# LED_Connection.net
KiCad netlist of a schematic drawn in Altium Designer
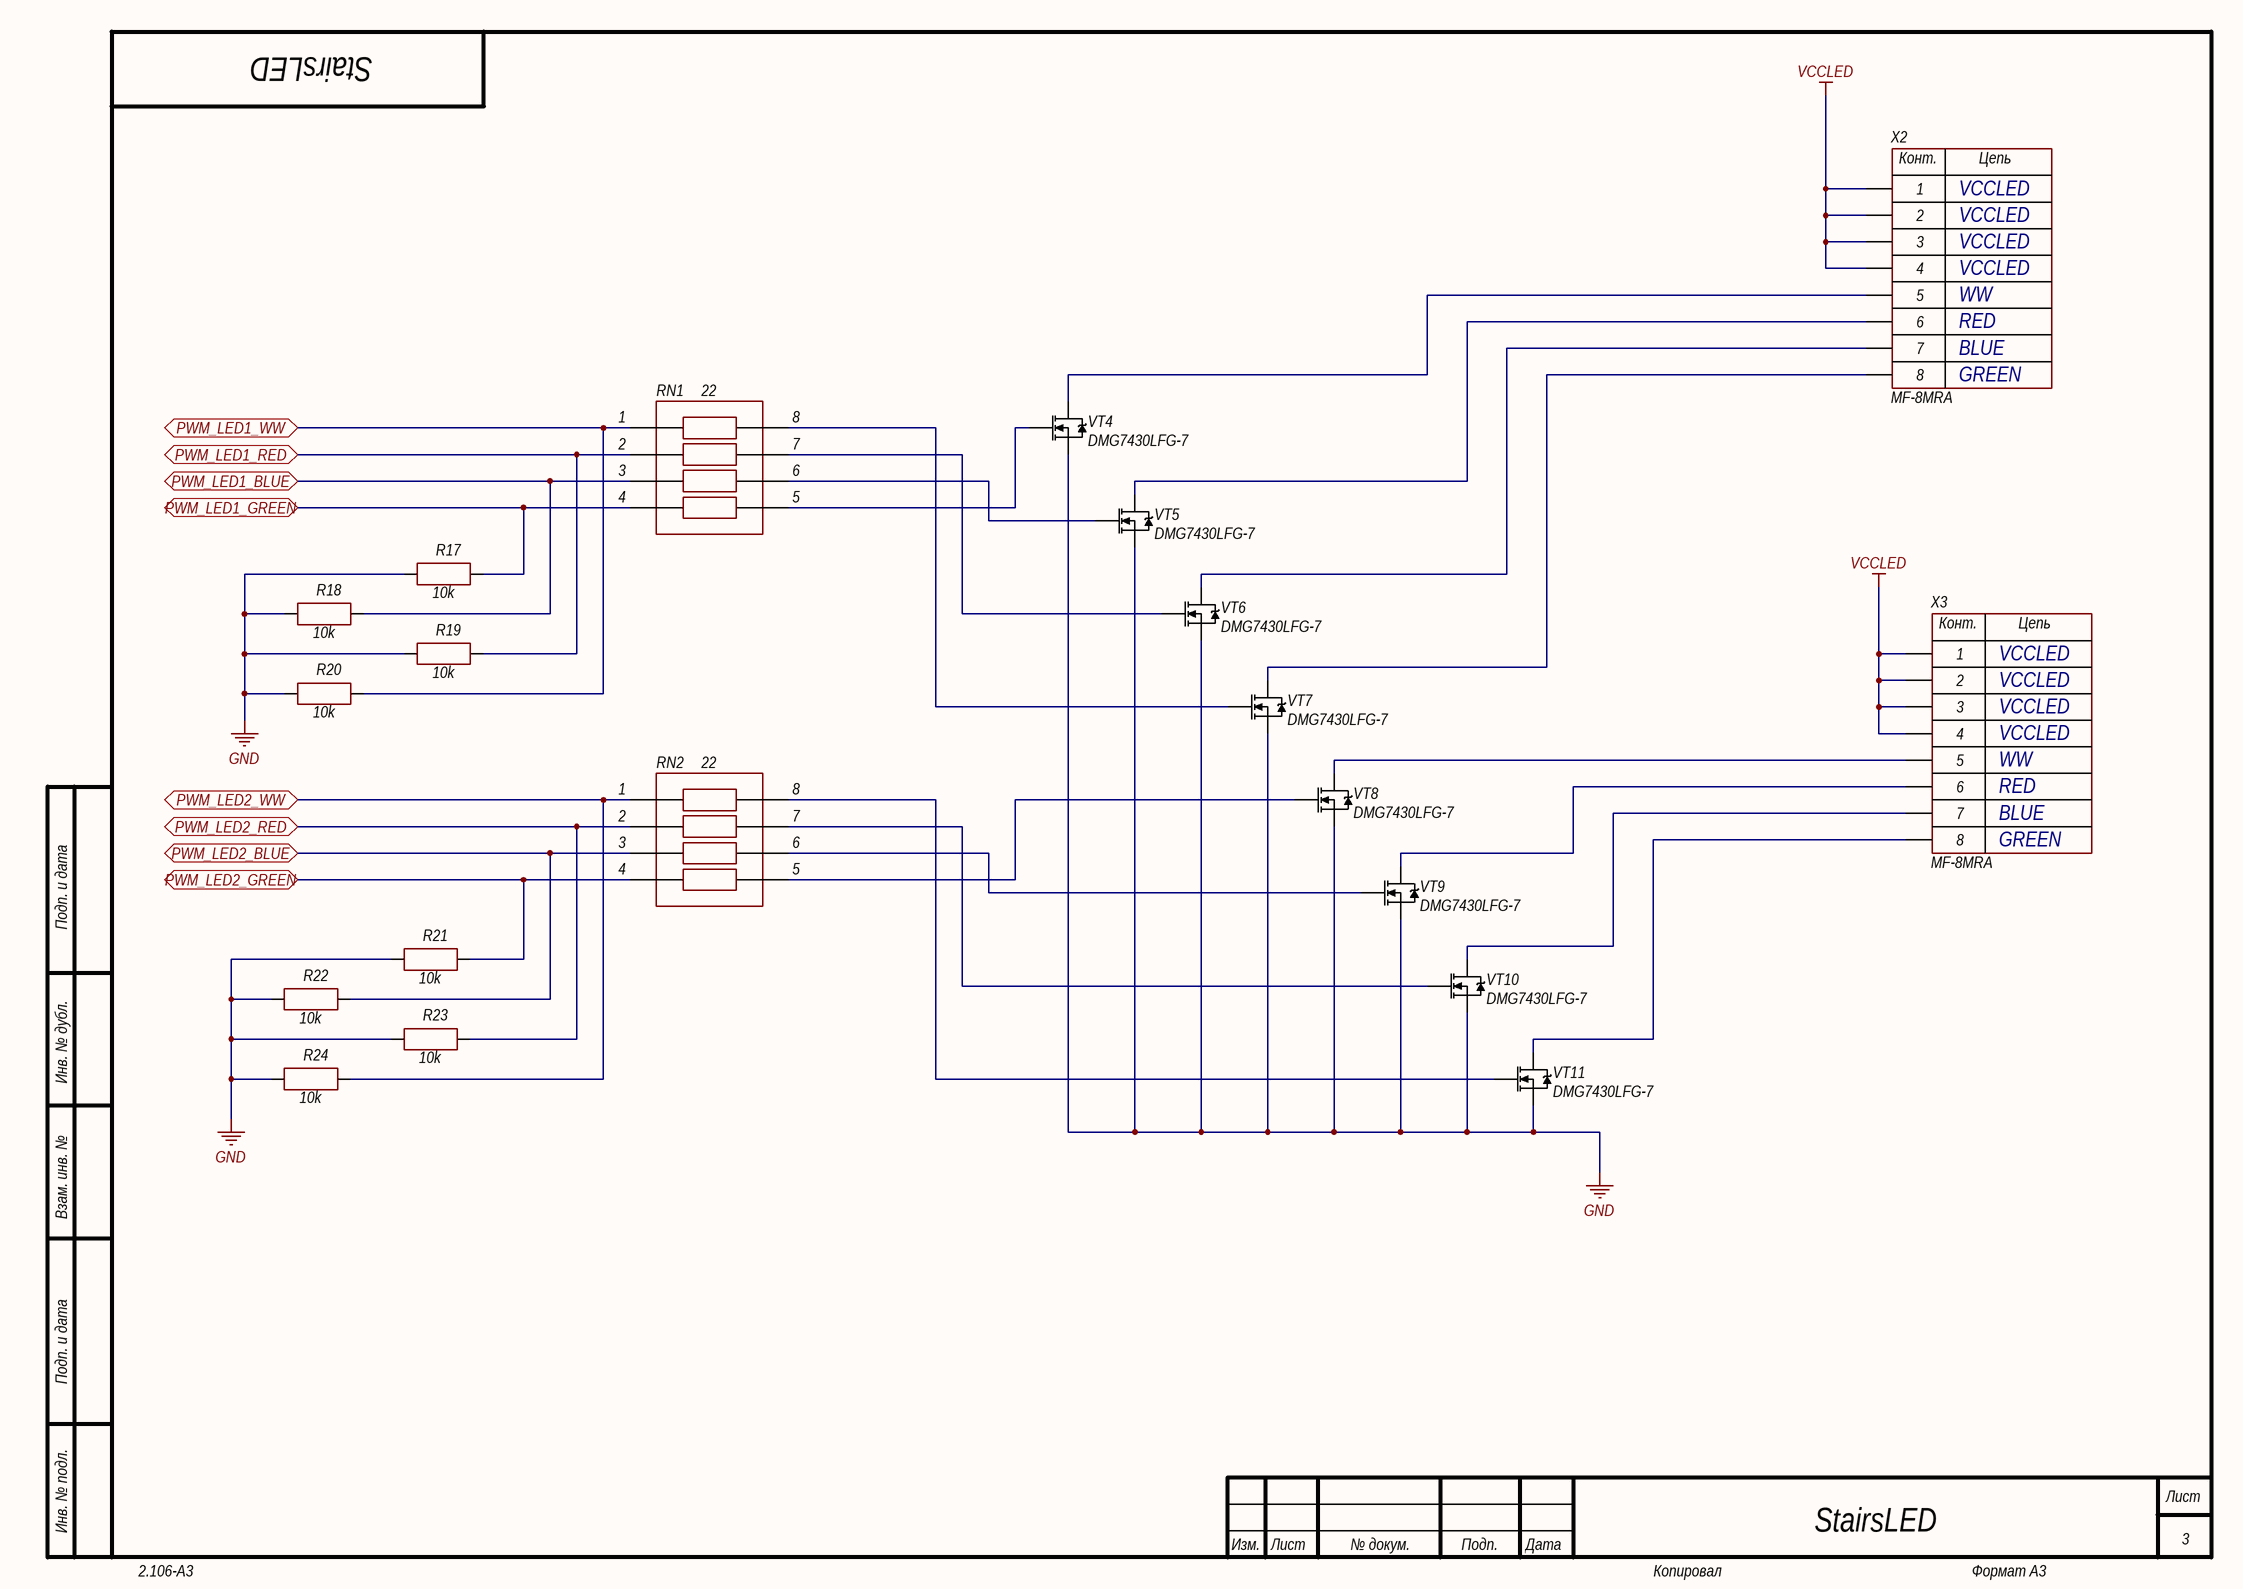
[diagram p0: LED Connection.SchDoc]

(export (version "E")
  (design (tool "Eeschema 10.0.6"))
  (components
    (comp (ref "R17") (value "10k") (footprint "CH0603R") (libsource (lib "Discrete") (part "Resistor")))
    (comp (ref "R18") (value "10k") (footprint "CH0603R") (libsource (lib "Discrete") (part "Resistor")))
    (comp (ref "R19") (value "10k") (footprint "CH0603R") (libsource (lib "Discrete") (part "Resistor")))
    (comp (ref "R20") (value "10k") (footprint "CH0603R") (libsource (lib "Discrete") (part "Resistor")))
    (comp (ref "R21") (value "10k") (footprint "CH0603R") (libsource (lib "Discrete") (part "Resistor")))
    (comp (ref "R22") (value "10k") (footprint "CH0603R") (libsource (lib "Discrete") (part "Resistor")))
    (comp (ref "R23") (value "10k") (footprint "CH0603R") (libsource (lib "Discrete") (part "Resistor")))
    (comp (ref "R24") (value "10k") (footprint "CH0603R") (libsource (lib "Discrete") (part "Resistor")))
    (comp (ref "RN1")
      (value "22")
      (footprint "CH0603Rx4 (1206)")
      (fields (field (name "MANUFACTURER") "Bourns GmbH."))
      (libsource (lib "Discrete") (part "Resistor assembly"))
    )
    (comp (ref "RN2")
      (value "22")
      (footprint "CH0603Rx4 (1206)")
      (fields (field (name "MANUFACTURER") "Bourns GmbH."))
      (libsource (lib "Discrete") (part "Resistor assembly"))
    )
    (comp (ref "VT4")
      (value "DMG7430LFG-7")
      (footprint "TRANS: PowerDI®3333-8")
      (description "Mosfet")
      (fields (field (name "MANUFACTURER") "Diodes Incorporated"))
      (libsource (lib "Transistor") (part "N-chanel"))
    )
    (comp (ref "VT5")
      (value "DMG7430LFG-7")
      (footprint "TRANS: PowerDI®3333-8")
      (description "Mosfet")
      (fields (field (name "MANUFACTURER") "Diodes Incorporated"))
      (libsource (lib "Transistor") (part "N-chanel"))
    )
    (comp (ref "VT6")
      (value "DMG7430LFG-7")
      (footprint "TRANS: PowerDI®3333-8")
      (description "Mosfet")
      (fields (field (name "MANUFACTURER") "Diodes Incorporated"))
      (libsource (lib "Transistor") (part "N-chanel"))
    )
    (comp (ref "VT7")
      (value "DMG7430LFG-7")
      (footprint "TRANS: PowerDI®3333-8")
      (description "Mosfet")
      (fields (field (name "MANUFACTURER") "Diodes Incorporated"))
      (libsource (lib "Transistor") (part "N-chanel"))
    )
    (comp (ref "VT8")
      (value "DMG7430LFG-7")
      (footprint "TRANS: PowerDI®3333-8")
      (description "Mosfet")
      (fields (field (name "MANUFACTURER") "Diodes Incorporated"))
      (libsource (lib "Transistor") (part "N-chanel"))
    )
    (comp (ref "VT9")
      (value "DMG7430LFG-7")
      (footprint "TRANS: PowerDI®3333-8")
      (description "Mosfet")
      (fields (field (name "MANUFACTURER") "Diodes Incorporated"))
      (libsource (lib "Transistor") (part "N-chanel"))
    )
    (comp (ref "VT10")
      (value "DMG7430LFG-7")
      (footprint "TRANS: PowerDI®3333-8")
      (description "Mosfet")
      (fields (field (name "MANUFACTURER") "Diodes Incorporated"))
      (libsource (lib "Transistor") (part "N-chanel"))
    )
    (comp (ref "VT11")
      (value "DMG7430LFG-7")
      (footprint "TRANS: PowerDI®3333-8")
      (description "Mosfet")
      (fields (field (name "MANUFACTURER") "Diodes Incorporated"))
      (libsource (lib "Transistor") (part "N-chanel"))
    )
    (comp (ref "X2")
      (value "MF-8MRA")
      (footprint "CON: MF-8MRA")
      (libsource (lib "Connectors") (part "8-Connector"))
    )
    (comp (ref "X3")
      (value "MF-8MRA")
      (footprint "CON: MF-8MRA")
      (libsource (lib "Connectors") (part "8-Connector"))
    )
  )
  (nets
    (net (code "1") (name "/PWM_LED1_BLUE") (class "Default")
      (node (ref "R18") (pin "2") (pinfunction "2_2") (pintype "passive"))
      (node (ref "RN1") (pin "3") (pinfunction "3_3") (pintype "passive"))
    )
    (net (code "2") (name "/PWM_LED1_GREEN") (class "Default")
      (node (ref "R17") (pin "2") (pinfunction "2_2") (pintype "passive"))
      (node (ref "RN1") (pin "4") (pinfunction "4_4") (pintype "passive"))
    )
    (net (code "3") (name "/PWM_LED1_RED") (class "Default")
      (node (ref "R19") (pin "2") (pinfunction "2_2") (pintype "passive"))
      (node (ref "RN1") (pin "2") (pinfunction "2_2") (pintype "passive"))
    )
    (net (code "4") (name "/PWM_LED1_WW") (class "Default")
      (node (ref "R20") (pin "2") (pinfunction "2_2") (pintype "passive"))
      (node (ref "RN1") (pin "1") (pinfunction "1_1") (pintype "passive"))
    )
    (net (code "5") (name "/PWM_LED2_BLUE") (class "Default")
      (node (ref "R22") (pin "2") (pinfunction "2_2") (pintype "passive"))
      (node (ref "RN2") (pin "3") (pinfunction "3_3") (pintype "passive"))
    )
    (net (code "6") (name "/PWM_LED2_GREEN") (class "Default")
      (node (ref "R21") (pin "2") (pinfunction "2_2") (pintype "passive"))
      (node (ref "RN2") (pin "4") (pinfunction "4_4") (pintype "passive"))
    )
    (net (code "7") (name "/PWM_LED2_RED") (class "Default")
      (node (ref "R23") (pin "2") (pinfunction "2_2") (pintype "passive"))
      (node (ref "RN2") (pin "2") (pinfunction "2_2") (pintype "passive"))
    )
    (net (code "8") (name "/PWM_LED2_WW") (class "Default")
      (node (ref "R24") (pin "2") (pinfunction "2_2") (pintype "passive"))
      (node (ref "RN2") (pin "1") (pinfunction "1_1") (pintype "passive"))
    )
    (net (code "9") (name "GND") (class "Default")
      (node (ref "R17") (pin "1") (pinfunction "1_1") (pintype "passive"))
      (node (ref "R18") (pin "1") (pinfunction "1_1") (pintype "passive"))
      (node (ref "R19") (pin "1") (pinfunction "1_1") (pintype "passive"))
      (node (ref "R20") (pin "1") (pinfunction "1_1") (pintype "passive"))
      (node (ref "R21") (pin "1") (pinfunction "1_1") (pintype "passive"))
      (node (ref "R22") (pin "1") (pinfunction "1_1") (pintype "passive"))
      (node (ref "R23") (pin "1") (pinfunction "1_1") (pintype "passive"))
      (node (ref "R24") (pin "1") (pinfunction "1_1") (pintype "passive"))
      (node (ref "VT10") (pin "3") (pinfunction "S_3") (pintype "passive"))
      (node (ref "VT11") (pin "3") (pinfunction "S_3") (pintype "passive"))
      (node (ref "VT4") (pin "3") (pinfunction "S_3") (pintype "passive"))
      (node (ref "VT5") (pin "3") (pinfunction "S_3") (pintype "passive"))
      (node (ref "VT6") (pin "3") (pinfunction "S_3") (pintype "passive"))
      (node (ref "VT7") (pin "3") (pinfunction "S_3") (pintype "passive"))
      (node (ref "VT8") (pin "3") (pinfunction "S_3") (pintype "passive"))
      (node (ref "VT9") (pin "3") (pinfunction "S_3") (pintype "passive"))
    )
    (net (code "10") (name "Net-(VT4-D)") (class "Default")
      (node (ref "VT4") (pin "2") (pinfunction "D_2") (pintype "passive"))
      (node (ref "X2") (pin "5") (pinfunction "5_5") (pintype "power_in"))
    )
    (net (code "11") (name "Net-(VT4-G)") (class "Default")
      (node (ref "RN1") (pin "5") (pinfunction "5_5") (pintype "passive"))
      (node (ref "VT4") (pin "1") (pinfunction "G_1") (pintype "passive"))
    )
    (net (code "12") (name "Net-(VT5-D)") (class "Default")
      (node (ref "VT5") (pin "2") (pinfunction "D_2") (pintype "passive"))
      (node (ref "X2") (pin "6") (pinfunction "6_6") (pintype "power_in"))
    )
    (net (code "13") (name "Net-(VT5-G)") (class "Default")
      (node (ref "RN1") (pin "6") (pinfunction "6_6") (pintype "passive"))
      (node (ref "VT5") (pin "1") (pinfunction "G_1") (pintype "passive"))
    )
    (net (code "14") (name "Net-(VT6-D)") (class "Default")
      (node (ref "VT6") (pin "2") (pinfunction "D_2") (pintype "passive"))
      (node (ref "X2") (pin "7") (pinfunction "7_7") (pintype "power_in"))
    )
    (net (code "15") (name "Net-(VT6-G)") (class "Default")
      (node (ref "RN1") (pin "7") (pinfunction "7_7") (pintype "passive"))
      (node (ref "VT6") (pin "1") (pinfunction "G_1") (pintype "passive"))
    )
    (net (code "16") (name "Net-(VT7-D)") (class "Default")
      (node (ref "VT7") (pin "2") (pinfunction "D_2") (pintype "passive"))
      (node (ref "X2") (pin "8") (pinfunction "8_8") (pintype "power_in"))
    )
    (net (code "17") (name "Net-(VT7-G)") (class "Default")
      (node (ref "RN1") (pin "8") (pinfunction "8_8") (pintype "passive"))
      (node (ref "VT7") (pin "1") (pinfunction "G_1") (pintype "passive"))
    )
    (net (code "18") (name "Net-(VT8-D)") (class "Default")
      (node (ref "VT8") (pin "2") (pinfunction "D_2") (pintype "passive"))
      (node (ref "X3") (pin "5") (pinfunction "5_5") (pintype "power_in"))
    )
    (net (code "19") (name "Net-(VT8-G)") (class "Default")
      (node (ref "RN2") (pin "5") (pinfunction "5_5") (pintype "passive"))
      (node (ref "VT8") (pin "1") (pinfunction "G_1") (pintype "passive"))
    )
    (net (code "20") (name "Net-(VT9-D)") (class "Default")
      (node (ref "VT9") (pin "2") (pinfunction "D_2") (pintype "passive"))
      (node (ref "X3") (pin "6") (pinfunction "6_6") (pintype "power_in"))
    )
    (net (code "21") (name "Net-(VT9-G)") (class "Default")
      (node (ref "RN2") (pin "6") (pinfunction "6_6") (pintype "passive"))
      (node (ref "VT9") (pin "1") (pinfunction "G_1") (pintype "passive"))
    )
    (net (code "22") (name "Net-(VT10-D)") (class "Default")
      (node (ref "VT10") (pin "2") (pinfunction "D_2") (pintype "passive"))
      (node (ref "X3") (pin "7") (pinfunction "7_7") (pintype "power_in"))
    )
    (net (code "23") (name "Net-(VT10-G)") (class "Default")
      (node (ref "RN2") (pin "7") (pinfunction "7_7") (pintype "passive"))
      (node (ref "VT10") (pin "1") (pinfunction "G_1") (pintype "passive"))
    )
    (net (code "24") (name "Net-(VT11-D)") (class "Default")
      (node (ref "VT11") (pin "2") (pinfunction "D_2") (pintype "passive"))
      (node (ref "X3") (pin "8") (pinfunction "8_8") (pintype "power_in"))
    )
    (net (code "25") (name "Net-(VT11-G)") (class "Default")
      (node (ref "RN2") (pin "8") (pinfunction "8_8") (pintype "passive"))
      (node (ref "VT11") (pin "1") (pinfunction "G_1") (pintype "passive"))
    )
    (net (code "26") (name "VCCLED") (class "Default")
      (node (ref "X2") (pin "1") (pinfunction "1_1") (pintype "passive"))
      (node (ref "X2") (pin "2") (pinfunction "2_2") (pintype "passive"))
      (node (ref "X2") (pin "3") (pinfunction "3_3") (pintype "power_in"))
      (node (ref "X2") (pin "4") (pinfunction "4_4") (pintype "power_in"))
      (node (ref "X3") (pin "1") (pinfunction "1_1") (pintype "passive"))
      (node (ref "X3") (pin "2") (pinfunction "2_2") (pintype "passive"))
      (node (ref "X3") (pin "3") (pinfunction "3_3") (pintype "power_in"))
      (node (ref "X3") (pin "4") (pinfunction "4_4") (pintype "power_in"))
    )
  )
)
